# Ham-Dip-003.net
KiCad netlist of a schematic drawn in EAGLE
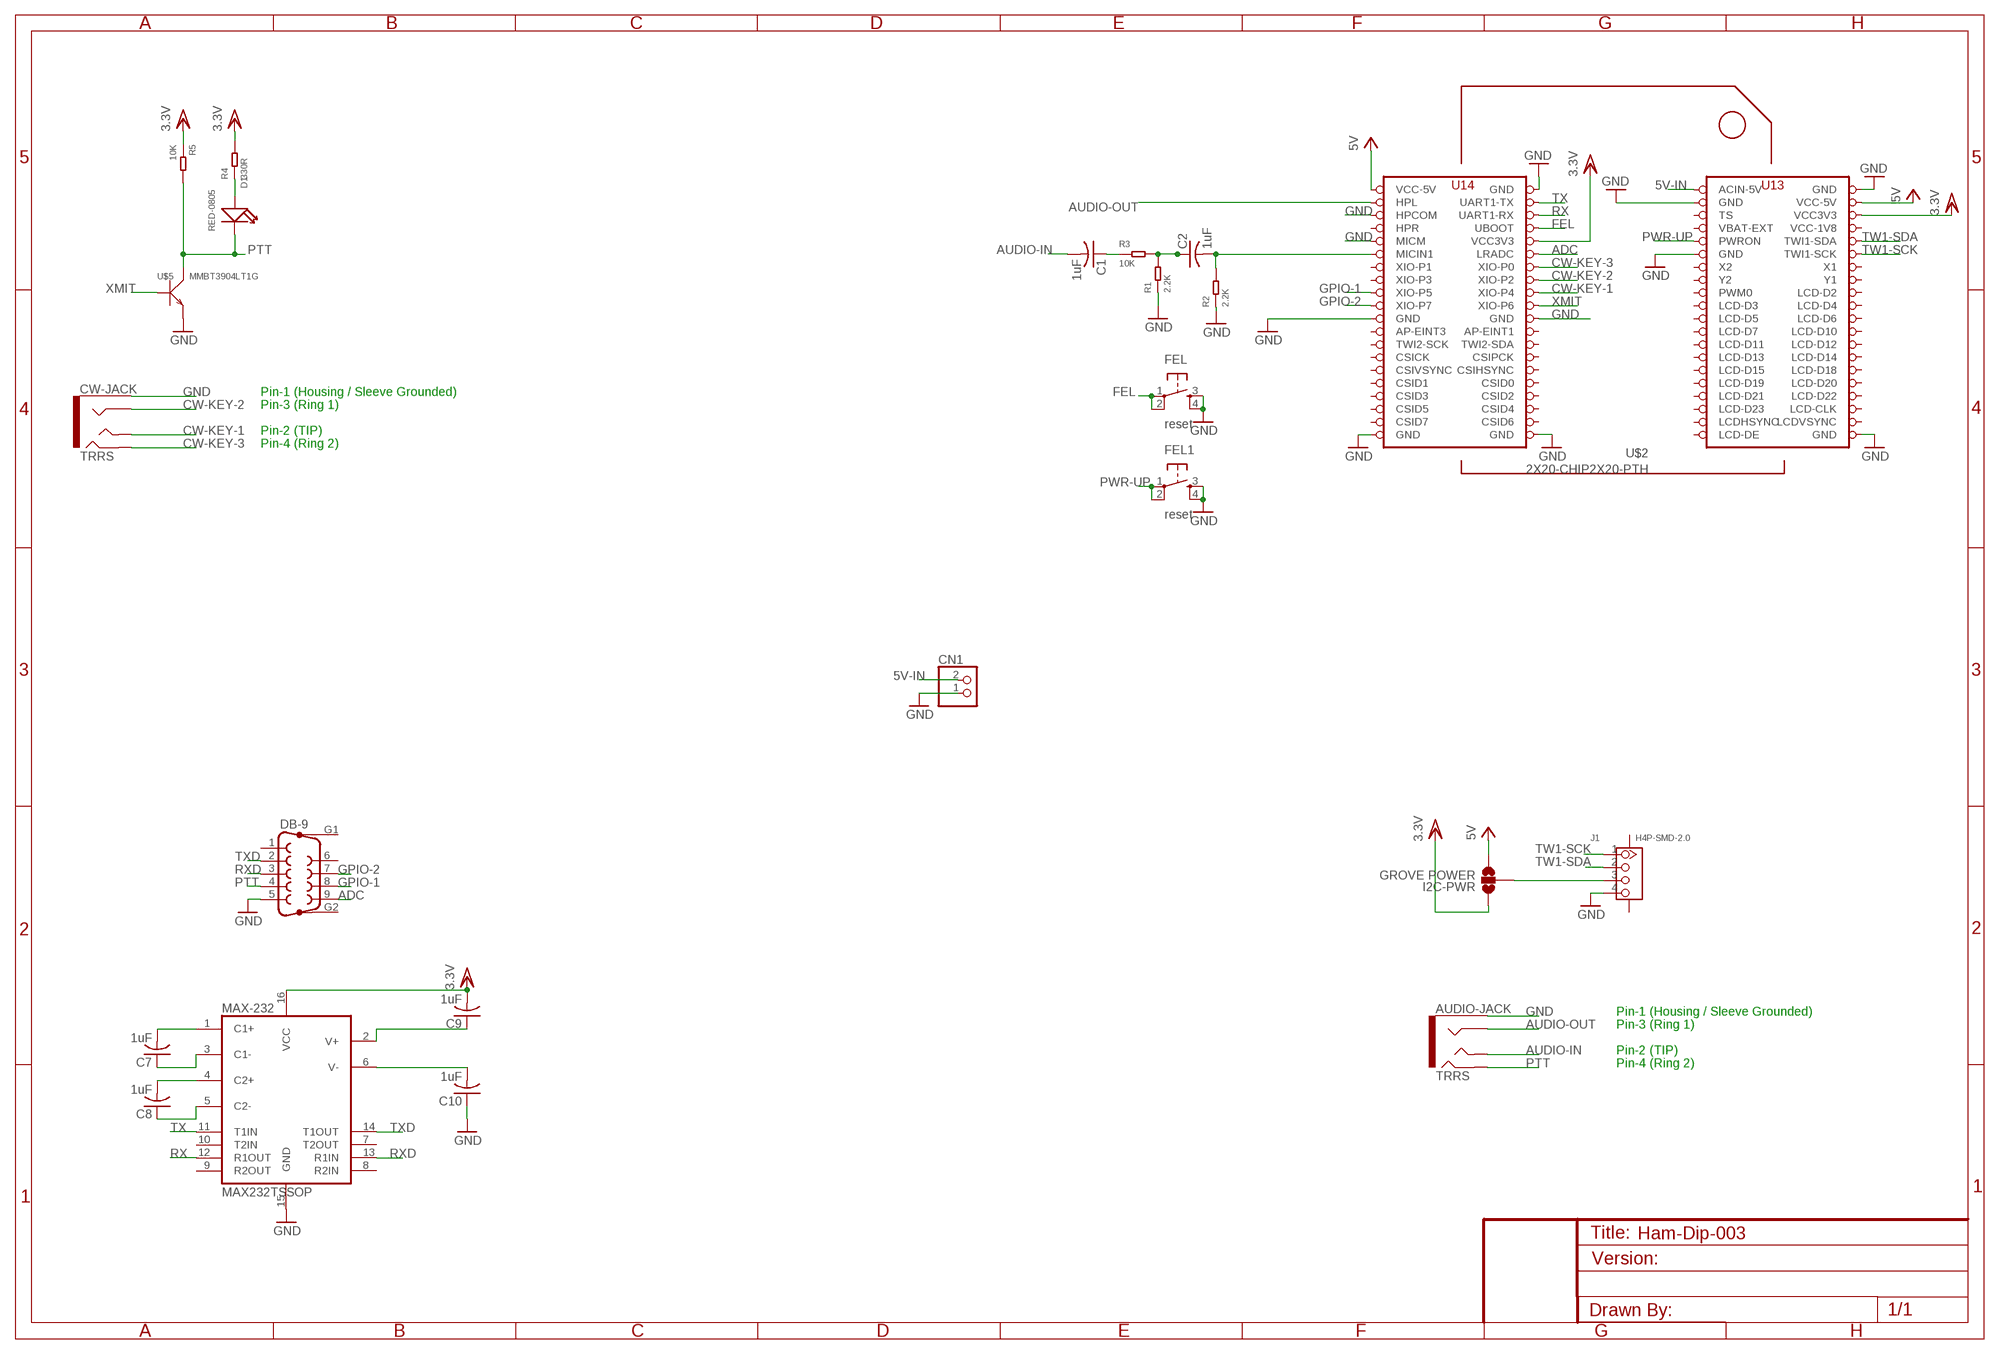
[diagram p0: schematic, sheet 1]

(export (version "E")
  (design (tool "Eeschema 10.0.6"))
  (components
    (comp (ref "AUDIO-JACK")
      (value "TRRS")
      (footprint "eagle-import:AUDIO-JACK-TRRS-SMD")
      (libsource (lib "eagle-import") (part "AUDIO-JACK3"))
    )
    (comp (ref "C1")
      (value "1uF")
      (footprint "eagle-import:C0805")
      (libsource (lib "eagle-import") (part "C-USC0805"))
    )
    (comp (ref "C2")
      (value "1uF")
      (footprint "eagle-import:C0805")
      (libsource (lib "eagle-import") (part "C-USC0805"))
    )
    (comp (ref "C7")
      (value "1uF")
      (footprint "eagle-import:C0805")
      (libsource (lib "eagle-import") (part "C-USC0805"))
    )
    (comp (ref "C8")
      (value "1uF")
      (footprint "eagle-import:C0805")
      (libsource (lib "eagle-import") (part "C-USC0805"))
    )
    (comp (ref "C9")
      (value "1uF")
      (footprint "eagle-import:C0805")
      (libsource (lib "eagle-import") (part "C-USC0805"))
    )
    (comp (ref "C10")
      (value "1uF")
      (footprint "eagle-import:C0805")
      (libsource (lib "eagle-import") (part "C-USC0805"))
    )
    (comp (ref "CN1")
      (value "JST_2PIN-SMT")
      (footprint "eagle-import:JST-PH-2-SMT")
      (libsource (lib "eagle-import") (part "JST_2PIN-SMT"))
    )
    (comp (ref "CW-JACK")
      (value "TRRS")
      (footprint "eagle-import:AUDIO-JACK-TRRS-SMD")
      (libsource (lib "eagle-import") (part "AUDIO-JACK3"))
    )
    (comp (ref "D1")
      (value "RED-0805")
      (footprint "eagle-import:LED-0805")
      (fields (field (name "MPN") "17-215SURC/S530-A2/TR8"))
      (libsource (lib "eagle-import") (part "SMD-LED-CLEAR-RED(0805)"))
    )
    (comp (ref "DB-9")
      (value "F09HP")
      (footprint "eagle-import:F09HP")
      (libsource (lib "eagle-import") (part "F09HP"))
    )
    (comp (ref "FEL")
      (value "reset")
      (footprint "eagle-import:TACTILE_SWITCH_SMD")
      (libsource (lib "eagle-import") (part "TAC_SWITCHSMD"))
    )
    (comp (ref "FEL1")
      (value "reset")
      (footprint "eagle-import:TACTILE_SWITCH_SMD")
      (libsource (lib "eagle-import") (part "TAC_SWITCHSMD"))
    )
    (comp (ref "I2C-PWR")
      (value "GROVE POWER")
      (footprint "eagle-import:SMD_SJ_3WAY_OPEN")
      (libsource (lib "eagle-import") (part "SMD_SJ_3WAY_OPENT"))
    )
    (comp (ref "J1")
      (value "H4P-SMD-2.0")
      (footprint "eagle-import:HW4-SMD-2.0")
      (libsource (lib "eagle-import") (part "GROVE-CONNECTOR-SMD(4+2P-2.0)"))
    )
    (comp (ref "MAX-232")
      (value "MAX232TSSOP")
      (footprint "eagle-import:TSSOP16")
      (libsource (lib "eagle-import") (part "MAX232TSSOP"))
    )
    (comp (ref "R1")
      (value "2.2K")
      (footprint "eagle-import:R0805")
      (fields (field (name "MPN") "RC0805JR-072K2L"))
      (libsource (lib "eagle-import") (part "SMD-RES-2.2K-5%-1/8W(0805)"))
    )
    (comp (ref "R2")
      (value "2.2K")
      (footprint "eagle-import:R0805")
      (fields (field (name "MPN") "RC0805JR-072K2L"))
      (libsource (lib "eagle-import") (part "SMD-RES-2.2K-5%-1/8W(0805)"))
    )
    (comp (ref "R3")
      (value "10K")
      (footprint "eagle-import:R0805")
      (fields (field (name "MPN") "RC0805FR-0710KL"))
      (libsource (lib "eagle-import") (part "SMD-RES-10K-1%-1/8W(0805)"))
    )
    (comp (ref "R4")
      (value "330R")
      (footprint "eagle-import:R0805")
      (fields (field (name "MPN") "RC0805JR-07220RL"))
      (libsource (lib "eagle-import") (part "SMD-RES-220R-5%-1/8W(0805)"))
    )
    (comp (ref "R5")
      (value "10K")
      (footprint "eagle-import:R0805")
      (fields (field (name "MPN") "RC0805FR-0710KL"))
      (libsource (lib "eagle-import") (part "SMD-RES-10K-1%-1/8W(0805)"))
    )
    (comp (ref "U$2")
      (value "2X20-CHIP2X20-PTH")
      (footprint "eagle-import:2X20CHIP-TH")
      (fields (field (name "VENDOR_PART_NUMBER") "AWHW40-G-SMD-R (single)"))
      (libsource (lib "eagle-import") (part "2X20-CHIP2X20-PTH-CHIP_A"))
    )
    (comp (ref "U$5")
      (value "MMBT3904LT1G")
      (footprint "eagle-import:SOT-23")
      (libsource (lib "eagle-import") (part "SMD-TRANSISTORS-NPN-40V-200MA-MMBT3904LT1G(SOT-23)"))
    )
  )
  (nets
    (net (code "1") (name "/5V-IN") (class "Default")
      (node (ref "CN1") (pin "2") (pinfunction "1_2") (pintype "passive"))
      (node (ref "U$2") (pin "CHG-IN") (pinfunction "ACIN-5V_CHG-IN") (pintype "passive"))
    )
    (net (code "2") (name "/ADC") (class "Default")
      (node (ref "DB-9") (pin "9") (pinfunction "9_9") (pintype "passive"))
      (node (ref "U$2") (pin "LRADC") (pinfunction "LRADC_LRADC") (pintype "passive"))
    )
    (net (code "3") (name "/AUDIO-IN") (class "Default")
      (node (ref "AUDIO-JACK") (pin "TIP") (pinfunction "TIP_TIP") (pintype "bidirectional"))
      (node (ref "C1") (pin "2") (pinfunction "2_2") (pintype "passive"))
    )
    (net (code "4") (name "/AUDIO-OUT") (class "Default")
      (node (ref "AUDIO-JACK") (pin "RING1") (pinfunction "RING1_RING1") (pintype "bidirectional"))
      (node (ref "U$2") (pin "HPL") (pinfunction "HPL_HPL") (pintype "passive"))
    )
    (net (code "5") (name "/CW-KEY-1") (class "Default")
      (node (ref "CW-JACK") (pin "TIP") (pinfunction "TIP_TIP") (pintype "bidirectional"))
      (node (ref "U$2") (pin "XIO-P4") (pinfunction "XIO-P4_XIO-P4") (pintype "passive"))
    )
    (net (code "6") (name "/CW-KEY-2") (class "Default")
      (node (ref "CW-JACK") (pin "RING1") (pinfunction "RING1_RING1") (pintype "bidirectional"))
      (node (ref "U$2") (pin "XIO-P2") (pinfunction "XIO-P2_XIO-P2") (pintype "passive"))
    )
    (net (code "7") (name "/CW-KEY-3") (class "Default")
      (node (ref "CW-JACK") (pin "RING2") (pinfunction "RING2_RING2") (pintype "bidirectional"))
      (node (ref "U$2") (pin "XIO-P0") (pinfunction "XIO-P0_XIO-P0") (pintype "passive"))
    )
    (net (code "8") (name "/FEL") (class "Default")
      (node (ref "FEL") (pin "1") (pinfunction "1_1") (pintype "passive"))
      (node (ref "FEL") (pin "2") (pinfunction "2_2") (pintype "passive"))
      (node (ref "U$2") (pin "FEL") (pinfunction "UBOOT_FEL") (pintype "passive"))
    )
    (net (code "9") (name "/GPIO-1") (class "Default")
      (node (ref "DB-9") (pin "8") (pinfunction "8_8") (pintype "passive"))
      (node (ref "U$2") (pin "XIO-P5") (pinfunction "XIO-P5_XIO-P5") (pintype "passive"))
    )
    (net (code "10") (name "/GPIO-2") (class "Default")
      (node (ref "DB-9") (pin "7") (pinfunction "7_7") (pintype "passive"))
      (node (ref "U$2") (pin "XIO-P7") (pinfunction "XIO-P7_XIO-P7") (pintype "passive"))
    )
    (net (code "11") (name "/PTT") (class "Default")
      (node (ref "AUDIO-JACK") (pin "RING2") (pinfunction "RING2_RING2") (pintype "bidirectional"))
      (node (ref "D1") (pin "-") (pinfunction "-_-") (pintype "passive"))
      (node (ref "DB-9") (pin "4") (pinfunction "4_4") (pintype "passive"))
      (node (ref "R5") (pin "2") (pinfunction "2_2") (pintype "passive"))
      (node (ref "U$5") (pin "3") (pinfunction "C_3") (pintype "passive"))
    )
    (net (code "12") (name "/PWR-UP") (class "Default")
      (node (ref "FEL1") (pin "1") (pinfunction "1_1") (pintype "passive"))
      (node (ref "FEL1") (pin "2") (pinfunction "2_2") (pintype "passive"))
      (node (ref "U$2") (pin "PWRON") (pinfunction "PWRON_PWRON") (pintype "passive"))
    )
    (net (code "13") (name "/RX") (class "Default")
      (node (ref "MAX-232") (pin "12") (pinfunction "R1OUT_12") (pintype "output"))
      (node (ref "U$2") (pin "UART1-RX") (pinfunction "UART1-RX_UART1-RX") (pintype "passive"))
    )
    (net (code "14") (name "/RXD") (class "Default")
      (node (ref "DB-9") (pin "3") (pinfunction "3_3") (pintype "passive"))
      (node (ref "MAX-232") (pin "13") (pinfunction "R1IN_13") (pintype "input"))
    )
    (net (code "15") (name "/TW1-SCK") (class "Default")
      (node (ref "J1") (pin "1") (pinfunction "1_1") (pintype "bidirectional"))
      (node (ref "U$2") (pin "TWI1-SCK") (pinfunction "TWI1-SCK_TWI1-SCK") (pintype "passive"))
    )
    (net (code "16") (name "/TW1-SDA") (class "Default")
      (node (ref "J1") (pin "2") (pinfunction "2_2") (pintype "bidirectional"))
      (node (ref "U$2") (pin "TWI1-SDA") (pinfunction "TWI1-SDA_TWI1-SDA") (pintype "passive"))
    )
    (net (code "17") (name "/TX") (class "Default")
      (node (ref "MAX-232") (pin "11") (pinfunction "T1IN_11") (pintype "input"))
      (node (ref "U$2") (pin "UART1-TX") (pinfunction "UART1-TX_UART1-TX") (pintype "passive"))
    )
    (net (code "18") (name "/TXD") (class "Default")
      (node (ref "DB-9") (pin "2") (pinfunction "2_2") (pintype "passive"))
      (node (ref "MAX-232") (pin "14") (pinfunction "T1OUT_14") (pintype "output"))
    )
    (net (code "19") (name "/VCC-1V8") (class "Default")
      (node (ref "U$2") (pin "VCC1V8") (pinfunction "VCC-1V8_VCC1V8") (pintype "power_in"))
    )
    (net (code "20") (name "/XMIT") (class "Default")
      (node (ref "U$2") (pin "XIO-P6") (pinfunction "XIO-P6_XIO-P6") (pintype "passive"))
      (node (ref "U$5") (pin "1") (pinfunction "B_1") (pintype "passive"))
    )
    (net (code "21") (name "3.3V") (class "Default")
      (node (ref "C9") (pin "2") (pinfunction "2_2") (pintype "passive"))
      (node (ref "I2C-PWR") (pin "1") (pinfunction "1_1") (pintype "passive"))
      (node (ref "MAX-232") (pin "16") (pinfunction "VCC_16") (pintype "bidirectional"))
      (node (ref "R4") (pin "2") (pinfunction "2_2") (pintype "passive"))
      (node (ref "R5") (pin "1") (pinfunction "1_1") (pintype "passive"))
      (node (ref "U$2") (pin "VCC3V3") (pinfunction "VCC3V3_VCC3V3") (pintype "power_in"))
      (node (ref "U$2") (pin "VCC3V3@1") (pinfunction "VCC3V3_VCC3V3@1") (pintype "power_in"))
    )
    (net (code "22") (name "5V") (class "Default")
      (node (ref "I2C-PWR") (pin "3") (pinfunction "3_3") (pintype "passive"))
      (node (ref "U$2") (pin "VCC5V@0") (pinfunction "VCC-5V_VCC5V@0") (pintype "power_in"))
      (node (ref "U$2") (pin "VCC5V@1") (pinfunction "VCC-5V_VCC5V@1") (pintype "power_in"))
    )
    (net (code "23") (name "GND") (class "Default")
      (node (ref "AUDIO-JACK") (pin "EARTH") (pinfunction "EARTH_EARTH") (pintype "bidirectional"))
      (node (ref "C10") (pin "1") (pinfunction "1_1") (pintype "passive"))
      (node (ref "CN1") (pin "1") (pinfunction "2_1") (pintype "passive"))
      (node (ref "CW-JACK") (pin "EARTH") (pinfunction "EARTH_EARTH") (pintype "bidirectional"))
      (node (ref "DB-9") (pin "5") (pinfunction "5_5") (pintype "passive"))
      (node (ref "FEL") (pin "3") (pinfunction "3_3") (pintype "passive"))
      (node (ref "FEL") (pin "4") (pinfunction "4_4") (pintype "passive"))
      (node (ref "FEL1") (pin "3") (pinfunction "3_3") (pintype "passive"))
      (node (ref "FEL1") (pin "4") (pinfunction "4_4") (pintype "passive"))
      (node (ref "J1") (pin "4") (pinfunction "4_4") (pintype "bidirectional"))
      (node (ref "MAX-232") (pin "15") (pinfunction "GND_15") (pintype "bidirectional"))
      (node (ref "R1") (pin "1") (pinfunction "1_1") (pintype "passive"))
      (node (ref "R2") (pin "1") (pinfunction "1_1") (pintype "passive"))
      (node (ref "U$2") (pin "GND@1") (pinfunction "GND_GND@1") (pintype "power_in"))
      (node (ref "U$2") (pin "GND@10") (pinfunction "GND_GND@10") (pintype "power_in"))
      (node (ref "U$2") (pin "GND@2") (pinfunction "GND_GND@2") (pintype "power_in"))
      (node (ref "U$2") (pin "GND@3") (pinfunction "GND_GND@3") (pintype "power_in"))
      (node (ref "U$2") (pin "GND@4") (pinfunction "GND_GND@4") (pintype "power_in"))
      (node (ref "U$2") (pin "GND@5") (pinfunction "GND_GND@5") (pintype "power_in"))
      (node (ref "U$2") (pin "GND@6") (pinfunction "GND_GND@6") (pintype "power_in"))
      (node (ref "U$2") (pin "GND@7") (pinfunction "GND_GND@7") (pintype "power_in"))
      (node (ref "U$2") (pin "GND@8") (pinfunction "GND_GND@8") (pintype "power_in"))
      (node (ref "U$2") (pin "HPCOM") (pinfunction "HPCOM_HPCOM") (pintype "passive"))
      (node (ref "U$2") (pin "MICM") (pinfunction "MICM_MICM") (pintype "passive"))
      (node (ref "U$5") (pin "2") (pinfunction "E_2") (pintype "passive"))
    )
    (net (code "24") (name "Net-(C1-Pad1)") (class "Default")
      (node (ref "C1") (pin "1") (pinfunction "1_1") (pintype "passive"))
      (node (ref "R3") (pin "1") (pinfunction "1_1") (pintype "passive"))
    )
    (net (code "25") (name "Net-(C2-Pad1)") (class "Default")
      (node (ref "C2") (pin "1") (pinfunction "1_1") (pintype "passive"))
      (node (ref "R1") (pin "2") (pinfunction "2_2") (pintype "passive"))
      (node (ref "R3") (pin "2") (pinfunction "2_2") (pintype "passive"))
    )
    (net (code "26") (name "Net-(C2-Pad2)") (class "Default")
      (node (ref "C2") (pin "2") (pinfunction "2_2") (pintype "passive"))
      (node (ref "R2") (pin "2") (pinfunction "2_2") (pintype "passive"))
      (node (ref "U$2") (pin "MICIN1") (pinfunction "MICIN1_MICIN1") (pintype "passive"))
    )
    (net (code "27") (name "Net-(D1-Pad+)") (class "Default")
      (node (ref "D1") (pin "+") (pinfunction "+_+") (pintype "passive"))
      (node (ref "R4") (pin "1") (pinfunction "1_1") (pintype "passive"))
    )
    (net (code "28") (name "Net-(I2C-PWR-Pad2)") (class "Default")
      (node (ref "I2C-PWR") (pin "2") (pinfunction "2_2") (pintype "passive"))
      (node (ref "J1") (pin "3") (pinfunction "3_3") (pintype "bidirectional"))
    )
    (net (code "29") (name "Net-(MAX-232-C1+)") (class "Default")
      (node (ref "C7") (pin "2") (pinfunction "2_2") (pintype "passive"))
      (node (ref "MAX-232") (pin "1") (pinfunction "C1+_1") (pintype "bidirectional"))
    )
    (net (code "30") (name "Net-(MAX-232-C1-)") (class "Default")
      (node (ref "C7") (pin "1") (pinfunction "1_1") (pintype "passive"))
      (node (ref "MAX-232") (pin "3") (pinfunction "C1-_3") (pintype "bidirectional"))
    )
    (net (code "31") (name "Net-(MAX-232-C2+)") (class "Default")
      (node (ref "C8") (pin "2") (pinfunction "2_2") (pintype "passive"))
      (node (ref "MAX-232") (pin "4") (pinfunction "C2+_4") (pintype "bidirectional"))
    )
    (net (code "32") (name "Net-(MAX-232-C2-)") (class "Default")
      (node (ref "C8") (pin "1") (pinfunction "1_1") (pintype "passive"))
      (node (ref "MAX-232") (pin "5") (pinfunction "C2-_5") (pintype "bidirectional"))
    )
    (net (code "33") (name "Net-(MAX-232-V+)") (class "Default")
      (node (ref "C9") (pin "1") (pinfunction "1_1") (pintype "passive"))
      (node (ref "MAX-232") (pin "2") (pinfunction "V+_2") (pintype "bidirectional"))
    )
    (net (code "34") (name "Net-(MAX-232-V-)") (class "Default")
      (node (ref "C10") (pin "2") (pinfunction "2_2") (pintype "passive"))
      (node (ref "MAX-232") (pin "6") (pinfunction "V-_6") (pintype "bidirectional"))
    )
    (net (code "35") (name "unconnected-(DB-9-Pad1)") (class "Default")
      (node (ref "DB-9") (pin "1") (pinfunction "1_1") (pintype "passive"))
    )
    (net (code "36") (name "unconnected-(DB-9-Pad6)") (class "Default")
      (node (ref "DB-9") (pin "6") (pinfunction "6_6") (pintype "passive"))
    )
    (net (code "37") (name "unconnected-(DB-9-PadG1)") (class "Default")
      (node (ref "DB-9") (pin "G1") (pinfunction "G1_G1") (pintype "passive"))
    )
    (net (code "38") (name "unconnected-(DB-9-PadG2)") (class "Default")
      (node (ref "DB-9") (pin "G2") (pinfunction "G2_G2") (pintype "passive"))
    )
    (net (code "39") (name "unconnected-(J1-PadSS1)") (class "Default")
      (node (ref "J1") (pin "SS1") (pinfunction "SS1_SS1") (pintype "bidirectional"))
    )
    (net (code "40") (name "unconnected-(J1-PadSS2)") (class "Default")
      (node (ref "J1") (pin "SS2") (pinfunction "SS2_SS2") (pintype "bidirectional"))
    )
    (net (code "41") (name "unconnected-(MAX-232-R2IN-Pad8)") (class "Default")
      (node (ref "MAX-232") (pin "8") (pinfunction "R2IN_8") (pintype "input"))
    )
    (net (code "42") (name "unconnected-(MAX-232-R2OUT-Pad9)") (class "Default")
      (node (ref "MAX-232") (pin "9") (pinfunction "R2OUT_9") (pintype "output"))
    )
    (net (code "43") (name "unconnected-(MAX-232-T2IN-Pad10)") (class "Default")
      (node (ref "MAX-232") (pin "10") (pinfunction "T2IN_10") (pintype "input"))
    )
    (net (code "44") (name "unconnected-(MAX-232-T2OUT-Pad7)") (class "Default")
      (node (ref "MAX-232") (pin "7") (pinfunction "T2OUT_7") (pintype "output"))
    )
    (net (code "45") (name "unconnected-(U$2-LCDHSYNC-PadLCD-HSYNC)") (class "Default")
      (node (ref "U$2") (pin "LCD-HSYNC") (pinfunction "LCDHSYNC_LCD-HSYNC") (pintype "passive"))
    )
    (net (code "46") (name "unconnected-(U$2-LCDVSYNC-PadLCD-VSYNC)") (class "Default")
      (node (ref "U$2") (pin "LCD-VSYNC") (pinfunction "LCDVSYNC_LCD-VSYNC") (pintype "passive"))
    )
    (net (code "47") (name "unconnected-(U$2-PadAP-EINT1)") (class "Default")
      (node (ref "U$2") (pin "AP-EINT1") (pinfunction "AP-EINT1_AP-EINT1") (pintype "passive"))
    )
    (net (code "48") (name "unconnected-(U$2-PadAP-EINT3)") (class "Default")
      (node (ref "U$2") (pin "AP-EINT3") (pinfunction "AP-EINT3_AP-EINT3") (pintype "passive"))
    )
    (net (code "49") (name "unconnected-(U$2-PadCSICK)") (class "Default")
      (node (ref "U$2") (pin "CSICK") (pinfunction "CSICK_CSICK") (pintype "passive"))
    )
    (net (code "50") (name "unconnected-(U$2-PadCSID0)") (class "Default")
      (node (ref "U$2") (pin "CSID0") (pinfunction "CSID0_CSID0") (pintype "passive"))
    )
    (net (code "51") (name "unconnected-(U$2-PadCSID1)") (class "Default")
      (node (ref "U$2") (pin "CSID1") (pinfunction "CSID1_CSID1") (pintype "passive"))
    )
    (net (code "52") (name "unconnected-(U$2-PadCSID2)") (class "Default")
      (node (ref "U$2") (pin "CSID2") (pinfunction "CSID2_CSID2") (pintype "passive"))
    )
    (net (code "53") (name "unconnected-(U$2-PadCSID3)") (class "Default")
      (node (ref "U$2") (pin "CSID3") (pinfunction "CSID3_CSID3") (pintype "passive"))
    )
    (net (code "54") (name "unconnected-(U$2-PadCSID4)") (class "Default")
      (node (ref "U$2") (pin "CSID4") (pinfunction "CSID4_CSID4") (pintype "passive"))
    )
    (net (code "55") (name "unconnected-(U$2-PadCSID5)") (class "Default")
      (node (ref "U$2") (pin "CSID5") (pinfunction "CSID5_CSID5") (pintype "passive"))
    )
    (net (code "56") (name "unconnected-(U$2-PadCSID6)") (class "Default")
      (node (ref "U$2") (pin "CSID6") (pinfunction "CSID6_CSID6") (pintype "passive"))
    )
    (net (code "57") (name "unconnected-(U$2-PadCSID7)") (class "Default")
      (node (ref "U$2") (pin "CSID7") (pinfunction "CSID7_CSID7") (pintype "passive"))
    )
    (net (code "58") (name "unconnected-(U$2-PadCSIHSYNC)") (class "Default")
      (node (ref "U$2") (pin "CSIHSYNC") (pinfunction "CSIHSYNC_CSIHSYNC") (pintype "passive"))
    )
    (net (code "59") (name "unconnected-(U$2-PadCSIPCK)") (class "Default")
      (node (ref "U$2") (pin "CSIPCK") (pinfunction "CSIPCK_CSIPCK") (pintype "passive"))
    )
    (net (code "60") (name "unconnected-(U$2-PadCSIVSYNC)") (class "Default")
      (node (ref "U$2") (pin "CSIVSYNC") (pinfunction "CSIVSYNC_CSIVSYNC") (pintype "passive"))
    )
    (net (code "61") (name "unconnected-(U$2-PadHPR)") (class "Default")
      (node (ref "U$2") (pin "HPR") (pinfunction "HPR_HPR") (pintype "passive"))
    )
    (net (code "62") (name "unconnected-(U$2-PadLCD-CLK)") (class "Default")
      (node (ref "U$2") (pin "LCD-CLK") (pinfunction "LCD-CLK_LCD-CLK") (pintype "passive"))
    )
    (net (code "63") (name "unconnected-(U$2-PadLCD-D2)") (class "Default")
      (node (ref "U$2") (pin "LCD-D2") (pinfunction "LCD-D2_LCD-D2") (pintype "passive"))
    )
    (net (code "64") (name "unconnected-(U$2-PadLCD-D3)") (class "Default")
      (node (ref "U$2") (pin "LCD-D3") (pinfunction "LCD-D3_LCD-D3") (pintype "passive"))
    )
    (net (code "65") (name "unconnected-(U$2-PadLCD-D4)") (class "Default")
      (node (ref "U$2") (pin "LCD-D4") (pinfunction "LCD-D4_LCD-D4") (pintype "passive"))
    )
    (net (code "66") (name "unconnected-(U$2-PadLCD-D5)") (class "Default")
      (node (ref "U$2") (pin "LCD-D5") (pinfunction "LCD-D5_LCD-D5") (pintype "passive"))
    )
    (net (code "67") (name "unconnected-(U$2-PadLCD-D6)") (class "Default")
      (node (ref "U$2") (pin "LCD-D6") (pinfunction "LCD-D6_LCD-D6") (pintype "passive"))
    )
    (net (code "68") (name "unconnected-(U$2-PadLCD-D7)") (class "Default")
      (node (ref "U$2") (pin "LCD-D7") (pinfunction "LCD-D7_LCD-D7") (pintype "passive"))
    )
    (net (code "69") (name "unconnected-(U$2-PadLCD-D10)") (class "Default")
      (node (ref "U$2") (pin "LCD-D10") (pinfunction "LCD-D10_LCD-D10") (pintype "passive"))
    )
    (net (code "70") (name "unconnected-(U$2-PadLCD-D11)") (class "Default")
      (node (ref "U$2") (pin "LCD-D11") (pinfunction "LCD-D11_LCD-D11") (pintype "passive"))
    )
    (net (code "71") (name "unconnected-(U$2-PadLCD-D12)") (class "Default")
      (node (ref "U$2") (pin "LCD-D12") (pinfunction "LCD-D12_LCD-D12") (pintype "passive"))
    )
    (net (code "72") (name "unconnected-(U$2-PadLCD-D13)") (class "Default")
      (node (ref "U$2") (pin "LCD-D13") (pinfunction "LCD-D13_LCD-D13") (pintype "passive"))
    )
    (net (code "73") (name "unconnected-(U$2-PadLCD-D14)") (class "Default")
      (node (ref "U$2") (pin "LCD-D14") (pinfunction "LCD-D14_LCD-D14") (pintype "passive"))
    )
    (net (code "74") (name "unconnected-(U$2-PadLCD-D15)") (class "Default")
      (node (ref "U$2") (pin "LCD-D15") (pinfunction "LCD-D15_LCD-D15") (pintype "passive"))
    )
    (net (code "75") (name "unconnected-(U$2-PadLCD-D18)") (class "Default")
      (node (ref "U$2") (pin "LCD-D18") (pinfunction "LCD-D18_LCD-D18") (pintype "passive"))
    )
    (net (code "76") (name "unconnected-(U$2-PadLCD-D19)") (class "Default")
      (node (ref "U$2") (pin "LCD-D19") (pinfunction "LCD-D19_LCD-D19") (pintype "passive"))
    )
    (net (code "77") (name "unconnected-(U$2-PadLCD-D20)") (class "Default")
      (node (ref "U$2") (pin "LCD-D20") (pinfunction "LCD-D20_LCD-D20") (pintype "passive"))
    )
    (net (code "78") (name "unconnected-(U$2-PadLCD-D21)") (class "Default")
      (node (ref "U$2") (pin "LCD-D21") (pinfunction "LCD-D21_LCD-D21") (pintype "passive"))
    )
    (net (code "79") (name "unconnected-(U$2-PadLCD-D22)") (class "Default")
      (node (ref "U$2") (pin "LCD-D22") (pinfunction "LCD-D22_LCD-D22") (pintype "passive"))
    )
    (net (code "80") (name "unconnected-(U$2-PadLCD-D23)") (class "Default")
      (node (ref "U$2") (pin "LCD-D23") (pinfunction "LCD-D23_LCD-D23") (pintype "passive"))
    )
    (net (code "81") (name "unconnected-(U$2-PadLCD-DE)") (class "Default")
      (node (ref "U$2") (pin "LCD-DE") (pinfunction "LCD-DE_LCD-DE") (pintype "passive"))
    )
    (net (code "82") (name "unconnected-(U$2-PadPWM0)") (class "Default")
      (node (ref "U$2") (pin "PWM0") (pinfunction "PWM0_PWM0") (pintype "passive"))
    )
    (net (code "83") (name "unconnected-(U$2-PadTS)") (class "Default")
      (node (ref "U$2") (pin "TS") (pinfunction "TS_TS") (pintype "passive"))
    )
    (net (code "84") (name "unconnected-(U$2-PadTWI2-SCK)") (class "Default")
      (node (ref "U$2") (pin "TWI2-SCK") (pinfunction "TWI2-SCK_TWI2-SCK") (pintype "passive"))
    )
    (net (code "85") (name "unconnected-(U$2-PadTWI2-SDA)") (class "Default")
      (node (ref "U$2") (pin "TWI2-SDA") (pinfunction "TWI2-SDA_TWI2-SDA") (pintype "passive"))
    )
    (net (code "86") (name "unconnected-(U$2-PadX1)") (class "Default")
      (node (ref "U$2") (pin "X1") (pinfunction "X1_X1") (pintype "passive"))
    )
    (net (code "87") (name "unconnected-(U$2-PadX2)") (class "Default")
      (node (ref "U$2") (pin "X2") (pinfunction "X2_X2") (pintype "passive"))
    )
    (net (code "88") (name "unconnected-(U$2-PadXIO-P1)") (class "Default")
      (node (ref "U$2") (pin "XIO-P1") (pinfunction "XIO-P1_XIO-P1") (pintype "passive"))
    )
    (net (code "89") (name "unconnected-(U$2-PadXIO-P3)") (class "Default")
      (node (ref "U$2") (pin "XIO-P3") (pinfunction "XIO-P3_XIO-P3") (pintype "passive"))
    )
    (net (code "90") (name "unconnected-(U$2-PadY1)") (class "Default")
      (node (ref "U$2") (pin "Y1") (pinfunction "Y1_Y1") (pintype "passive"))
    )
    (net (code "91") (name "unconnected-(U$2-PadY2)") (class "Default")
      (node (ref "U$2") (pin "Y2") (pinfunction "Y2_Y2") (pintype "passive"))
    )
    (net (code "92") (name "unconnected-(U$2-VBAT-EXT-PadBAT)") (class "Default")
      (node (ref "U$2") (pin "BAT") (pinfunction "VBAT-EXT_BAT") (pintype "passive"))
    )
  )
)
